# BigClown_WiFi_module.net
KiCad netlist of a schematic drawn in EAGLE
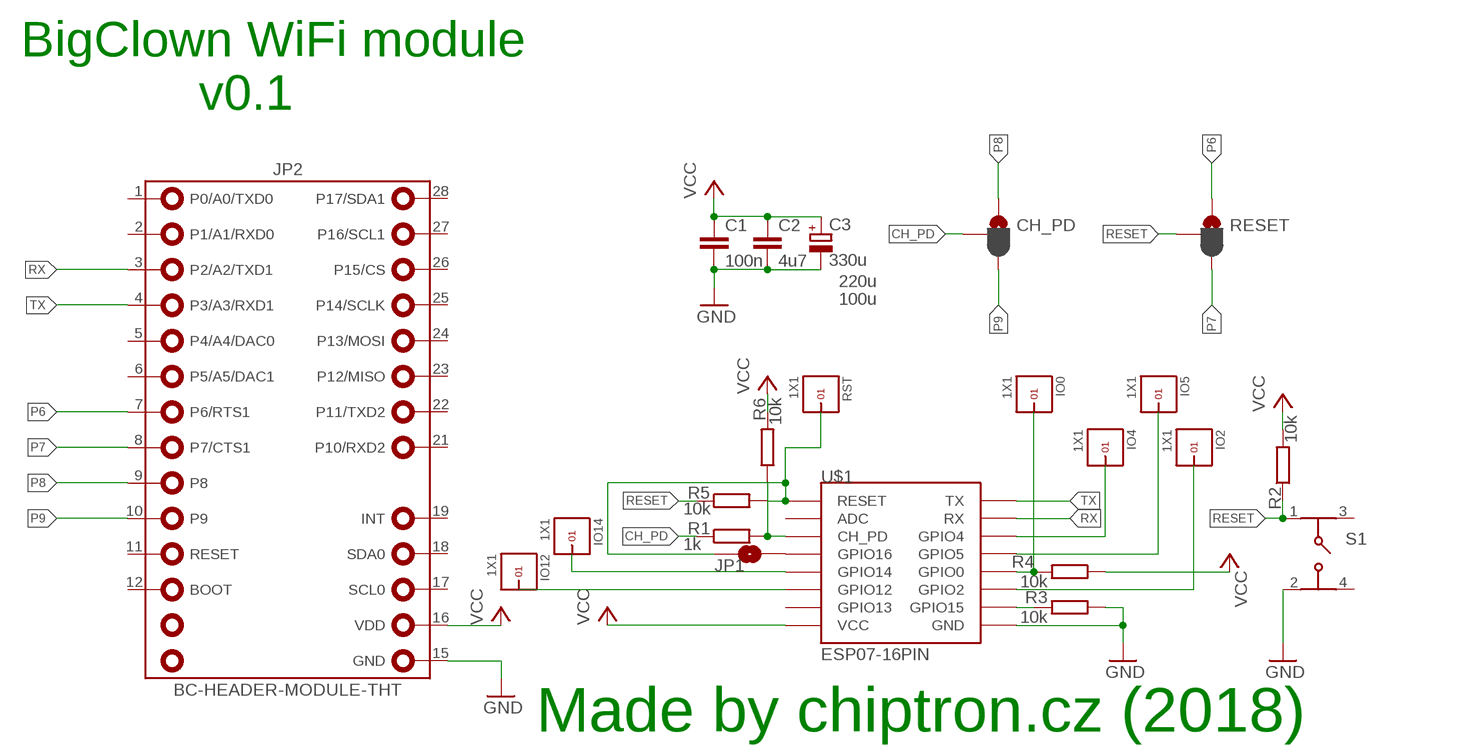
[diagram p0: schematic, sheet 1]

(export (version "E")
  (design (tool "Eeschema 10.0.6"))
  (components
    (comp (ref "C1")
      (value "100n")
      (footprint "eagle-import:C0805")
      (libsource (lib "eagle-import") (part "C-EUC0805"))
    )
    (comp (ref "C2")
      (value "4u7")
      (footprint "eagle-import:C1812K")
      (libsource (lib "eagle-import") (part "C-EUC1812K"))
    )
    (comp (ref "C3")
      (value "330u")
      (footprint "eagle-import:D_7343-31R")
      (libsource (lib "eagle-import") (part "CPOL-EUD/7343-31R"))
    )
    (comp (ref "CH_PD")
      (value "JUMPER-SMT_3_1-NC_PASTE_SILK")
      (footprint "eagle-import:SMT-JUMPER_3_1-NC_PASTE_SILK")
      (libsource (lib "eagle-import") (part "JUMPER-SMT_3_1-NC_PASTE_SILK"))
    )
    (comp (ref "IO0")
      (value "1X1")
      (footprint "eagle-import:1X1")
      (libsource (lib "eagle-import") (part "1X1"))
    )
    (comp (ref "IO2")
      (value "1X1")
      (footprint "eagle-import:1X1")
      (libsource (lib "eagle-import") (part "1X1"))
    )
    (comp (ref "IO4")
      (value "1X1")
      (footprint "eagle-import:1X1")
      (libsource (lib "eagle-import") (part "1X1"))
    )
    (comp (ref "IO5")
      (value "1X1")
      (footprint "eagle-import:1X1")
      (libsource (lib "eagle-import") (part "1X1"))
    )
    (comp (ref "IO12")
      (value "1X1")
      (footprint "eagle-import:1X1")
      (libsource (lib "eagle-import") (part "1X1"))
    )
    (comp (ref "IO14")
      (value "1X1")
      (footprint "eagle-import:1X1")
      (libsource (lib "eagle-import") (part "1X1"))
    )
    (comp (ref "JP1")
      (value "JUMPER-SMT_2_NO_NO-SILK")
      (footprint "eagle-import:SMT-JUMPER_2_NO_NO-SILK")
      (libsource (lib "eagle-import") (part "JUMPER-SMT_2_NO_NO-SILK"))
    )
    (comp (ref "JP2")
      (value "BC-HEADER-MODULE-THT")
      (footprint "eagle-import:BC-HEADER-MODULE-THT")
      (libsource (lib "eagle-import") (part "BC-HEADER-MODULE-THT"))
    )
    (comp (ref "R1")
      (value "1k")
      (footprint "eagle-import:M0805")
      (libsource (lib "eagle-import") (part "R-EU_M0805"))
    )
    (comp (ref "R2")
      (value "10k")
      (footprint "eagle-import:M0805")
      (libsource (lib "eagle-import") (part "R-EU_M0805"))
    )
    (comp (ref "R3")
      (value "10k")
      (footprint "eagle-import:M0805")
      (libsource (lib "eagle-import") (part "R-EU_M0805"))
    )
    (comp (ref "R4")
      (value "10k")
      (footprint "eagle-import:M0805")
      (libsource (lib "eagle-import") (part "R-EU_M0805"))
    )
    (comp (ref "R5")
      (value "10k")
      (footprint "eagle-import:M0805")
      (libsource (lib "eagle-import") (part "R-EU_M0805"))
    )
    (comp (ref "R6")
      (value "10k")
      (footprint "eagle-import:M0805")
      (libsource (lib "eagle-import") (part "R-EU_M0805"))
    )
    (comp (ref "RESET")
      (value "JUMPER-SMT_3_1-NC_PASTE_SILK")
      (footprint "eagle-import:SMT-JUMPER_3_1-NC_PASTE_SILK")
      (libsource (lib "eagle-import") (part "JUMPER-SMT_3_1-NC_PASTE_SILK"))
    )
    (comp (ref "RST")
      (value "1X1")
      (footprint "eagle-import:1X1")
      (libsource (lib "eagle-import") (part "1X1"))
    )
    (comp (ref "S1")
      (value "430152043826")
      (footprint "eagle-import:430152043826")
      (libsource (lib "eagle-import") (part "430152043826"))
    )
    (comp (ref "U$1")
      (value "ESP07-16PIN")
      (footprint "eagle-import:ESP07-16PIN")
      (libsource (lib "eagle-import") (part "ESP07-16PIN"))
    )
  )
  (nets
    (net (code "1") (name "CH_PD") (class "Default")
      (node (ref "CH_PD") (pin "2") (pinfunction "2_2") (pintype "passive"))
      (node (ref "R1") (pin "1") (pinfunction "1_1") (pintype "passive"))
    )
    (net (code "2") (name "GND") (class "Default")
      (node (ref "C1") (pin "2") (pinfunction "2_2") (pintype "passive"))
      (node (ref "C2") (pin "2") (pinfunction "2_2") (pintype "passive"))
      (node (ref "C3") (pin "-") (pinfunction "-_-") (pintype "passive"))
      (node (ref "JP2") (pin "15") (pinfunction "GND_15") (pintype "passive"))
      (node (ref "R3") (pin "1") (pinfunction "1_1") (pintype "passive"))
      (node (ref "S1") (pin "2") (pinfunction "2_2") (pintype "passive"))
      (node (ref "U$1") (pin "GND") (pinfunction "GND_GND") (pintype "bidirectional"))
    )
    (net (code "3") (name "Net-(IO0-Pad1)") (class "Default")
      (node (ref "IO0") (pin "1") (pinfunction "1_1") (pintype "bidirectional"))
      (node (ref "R4") (pin "2") (pinfunction "2_2") (pintype "passive"))
      (node (ref "U$1") (pin "GPIO0") (pinfunction "GPIO0_GPIO0") (pintype "bidirectional"))
    )
    (net (code "4") (name "Net-(IO2-Pad1)") (class "Default")
      (node (ref "IO2") (pin "1") (pinfunction "1_1") (pintype "bidirectional"))
      (node (ref "U$1") (pin "GPIO2") (pinfunction "GPIO2_GPIO2") (pintype "bidirectional"))
    )
    (net (code "5") (name "Net-(IO4-Pad1)") (class "Default")
      (node (ref "IO4") (pin "1") (pinfunction "1_1") (pintype "bidirectional"))
      (node (ref "U$1") (pin "GPIO4") (pinfunction "GPIO4_GPIO4") (pintype "bidirectional"))
    )
    (net (code "6") (name "Net-(IO5-Pad1)") (class "Default")
      (node (ref "IO5") (pin "1") (pinfunction "1_1") (pintype "bidirectional"))
      (node (ref "U$1") (pin "GPIO5") (pinfunction "GPIO5_GPIO5") (pintype "bidirectional"))
    )
    (net (code "7") (name "Net-(IO12-Pad1)") (class "Default")
      (node (ref "IO12") (pin "1") (pinfunction "1_1") (pintype "bidirectional"))
      (node (ref "U$1") (pin "GPIO12") (pinfunction "GPIO12_GPIO12") (pintype "bidirectional"))
    )
    (net (code "8") (name "Net-(IO14-Pad1)") (class "Default")
      (node (ref "IO14") (pin "1") (pinfunction "1_1") (pintype "bidirectional"))
      (node (ref "U$1") (pin "GPIO14") (pinfunction "GPIO14_GPIO14") (pintype "bidirectional"))
    )
    (net (code "9") (name "Net-(JP1-Pad2)") (class "Default")
      (node (ref "JP1") (pin "2") (pinfunction "2_2") (pintype "passive"))
      (node (ref "U$1") (pin "GPIO16") (pinfunction "GPIO16_GPIO16") (pintype "bidirectional"))
    )
    (net (code "10") (name "Net-(R1-Pad2)") (class "Default")
      (node (ref "R1") (pin "2") (pinfunction "2_2") (pintype "passive"))
      (node (ref "R6") (pin "1") (pinfunction "1_1") (pintype "passive"))
      (node (ref "U$1") (pin "CH_PD") (pinfunction "CH_PD_CH_PD") (pintype "bidirectional"))
    )
    (net (code "11") (name "Net-(R3-Pad2)") (class "Default")
      (node (ref "R3") (pin "2") (pinfunction "2_2") (pintype "passive"))
      (node (ref "U$1") (pin "GPIO15") (pinfunction "GPIO15_GPIO15") (pintype "bidirectional"))
    )
    (net (code "12") (name "Net-(U$1-RESET)") (class "Default")
      (node (ref "JP1") (pin "1") (pinfunction "1_1") (pintype "passive"))
      (node (ref "R5") (pin "2") (pinfunction "2_2") (pintype "passive"))
      (node (ref "RST") (pin "1") (pinfunction "1_1") (pintype "bidirectional"))
      (node (ref "U$1") (pin "REST") (pinfunction "RESET_REST") (pintype "bidirectional"))
    )
    (net (code "13") (name "P6") (class "Default")
      (node (ref "JP2") (pin "7") (pinfunction "P6/RTS1_7") (pintype "passive"))
      (node (ref "RESET") (pin "1") (pinfunction "1_1") (pintype "passive"))
    )
    (net (code "14") (name "P7") (class "Default")
      (node (ref "JP2") (pin "8") (pinfunction "P7/CTS1_8") (pintype "passive"))
      (node (ref "RESET") (pin "3") (pinfunction "3_3") (pintype "passive"))
    )
    (net (code "15") (name "P8") (class "Default")
      (node (ref "CH_PD") (pin "1") (pinfunction "1_1") (pintype "passive"))
      (node (ref "JP2") (pin "9") (pinfunction "P8_9") (pintype "passive"))
    )
    (net (code "16") (name "P9") (class "Default")
      (node (ref "CH_PD") (pin "3") (pinfunction "3_3") (pintype "passive"))
      (node (ref "JP2") (pin "10") (pinfunction "P9_10") (pintype "passive"))
    )
    (net (code "17") (name "RESET") (class "Default")
      (node (ref "R2") (pin "1") (pinfunction "1_1") (pintype "passive"))
      (node (ref "R5") (pin "1") (pinfunction "1_1") (pintype "passive"))
      (node (ref "RESET") (pin "2") (pinfunction "2_2") (pintype "passive"))
      (node (ref "S1") (pin "1") (pinfunction "1_1") (pintype "passive"))
    )
    (net (code "18") (name "RX") (class "Default")
      (node (ref "JP2") (pin "3") (pinfunction "P2/A2/TXD1_3") (pintype "passive"))
      (node (ref "U$1") (pin "RX") (pinfunction "RX_RX") (pintype "bidirectional"))
    )
    (net (code "19") (name "TX") (class "Default")
      (node (ref "JP2") (pin "4") (pinfunction "P3/A3/RXD1_4") (pintype "passive"))
      (node (ref "U$1") (pin "TX") (pinfunction "TX_TX") (pintype "bidirectional"))
    )
    (net (code "20") (name "VCC") (class "Default")
      (node (ref "C1") (pin "1") (pinfunction "1_1") (pintype "passive"))
      (node (ref "C2") (pin "1") (pinfunction "1_1") (pintype "passive"))
      (node (ref "C3") (pin "+") (pinfunction "+_+") (pintype "passive"))
      (node (ref "JP2") (pin "16") (pinfunction "VDD_16") (pintype "passive"))
      (node (ref "R2") (pin "2") (pinfunction "2_2") (pintype "passive"))
      (node (ref "R4") (pin "1") (pinfunction "1_1") (pintype "passive"))
      (node (ref "R6") (pin "2") (pinfunction "2_2") (pintype "passive"))
      (node (ref "U$1") (pin "VCC") (pinfunction "VCC_VCC") (pintype "bidirectional"))
    )
    (net (code "21") (name "unconnected-(JP2-BOOT-Pad12)") (class "Default")
      (node (ref "JP2") (pin "12") (pinfunction "BOOT_12") (pintype "passive"))
    )
    (net (code "22") (name "unconnected-(JP2-INT-Pad19)") (class "Default")
      (node (ref "JP2") (pin "19") (pinfunction "INT_19") (pintype "passive"))
    )
    (net (code "23") (name "unconnected-(JP2-P0{slash}A0{slash}TXD0-Pad1)") (class "Default")
      (node (ref "JP2") (pin "1") (pinfunction "P0/A0/TXD0_1") (pintype "passive"))
    )
    (net (code "24") (name "unconnected-(JP2-P1{slash}A1{slash}RXD03-Pad2)") (class "Default")
      (node (ref "JP2") (pin "2") (pinfunction "P1/A1/RXD03_2") (pintype "passive"))
    )
    (net (code "25") (name "unconnected-(JP2-P4{slash}A4{slash}DAC0-Pad5)") (class "Default")
      (node (ref "JP2") (pin "5") (pinfunction "P4/A4/DAC0_5") (pintype "passive"))
    )
    (net (code "26") (name "unconnected-(JP2-P5{slash}A5{slash}DAC1-Pad6)") (class "Default")
      (node (ref "JP2") (pin "6") (pinfunction "P5/A5/DAC1_6") (pintype "passive"))
    )
    (net (code "27") (name "unconnected-(JP2-P10{slash}RXD2-Pad21)") (class "Default")
      (node (ref "JP2") (pin "21") (pinfunction "P10/RXD2_21") (pintype "passive"))
    )
    (net (code "28") (name "unconnected-(JP2-P11{slash}TXD2-Pad22)") (class "Default")
      (node (ref "JP2") (pin "22") (pinfunction "P11/TXD2_22") (pintype "passive"))
    )
    (net (code "29") (name "unconnected-(JP2-P12{slash}MISO-Pad23)") (class "Default")
      (node (ref "JP2") (pin "23") (pinfunction "P12/MISO_23") (pintype "passive"))
    )
    (net (code "30") (name "unconnected-(JP2-P13{slash}MOSI-Pad24)") (class "Default")
      (node (ref "JP2") (pin "24") (pinfunction "P13/MOSI_24") (pintype "passive"))
    )
    (net (code "31") (name "unconnected-(JP2-P14{slash}SCLK-Pad25)") (class "Default")
      (node (ref "JP2") (pin "25") (pinfunction "P14/SCLK_25") (pintype "passive"))
    )
    (net (code "32") (name "unconnected-(JP2-P15{slash}CS-Pad26)") (class "Default")
      (node (ref "JP2") (pin "26") (pinfunction "P15/CS_26") (pintype "passive"))
    )
    (net (code "33") (name "unconnected-(JP2-P16{slash}SCL1-Pad27)") (class "Default")
      (node (ref "JP2") (pin "27") (pinfunction "P16/SCL1_27") (pintype "passive"))
    )
    (net (code "34") (name "unconnected-(JP2-P17{slash}SDA1-Pad28)") (class "Default")
      (node (ref "JP2") (pin "28") (pinfunction "P17/SDA1_28") (pintype "passive"))
    )
    (net (code "35") (name "unconnected-(JP2-RESET-Pad11)") (class "Default")
      (node (ref "JP2") (pin "11") (pinfunction "RESET_11") (pintype "passive"))
    )
    (net (code "36") (name "unconnected-(JP2-SCL0-Pad17)") (class "Default")
      (node (ref "JP2") (pin "17") (pinfunction "SCL0_17") (pintype "passive"))
    )
    (net (code "37") (name "unconnected-(JP2-SDA0-Pad18)") (class "Default")
      (node (ref "JP2") (pin "18") (pinfunction "SDA0_18") (pintype "passive"))
    )
    (net (code "38") (name "unconnected-(S1-Pad3)") (class "Default")
      (node (ref "S1") (pin "3") (pinfunction "3_3") (pintype "passive"))
    )
    (net (code "39") (name "unconnected-(S1-Pad4)") (class "Default")
      (node (ref "S1") (pin "4") (pinfunction "4_4") (pintype "passive"))
    )
    (net (code "40") (name "unconnected-(U$1-PadADC)") (class "Default")
      (node (ref "U$1") (pin "ADC") (pinfunction "ADC_ADC") (pintype "bidirectional"))
    )
    (net (code "41") (name "unconnected-(U$1-PadGPIO13)") (class "Default")
      (node (ref "U$1") (pin "GPIO13") (pinfunction "GPIO13_GPIO13") (pintype "bidirectional"))
    )
  )
)
